# untitled4.net
KiCad netlist of a schematic drawn in EAGLE
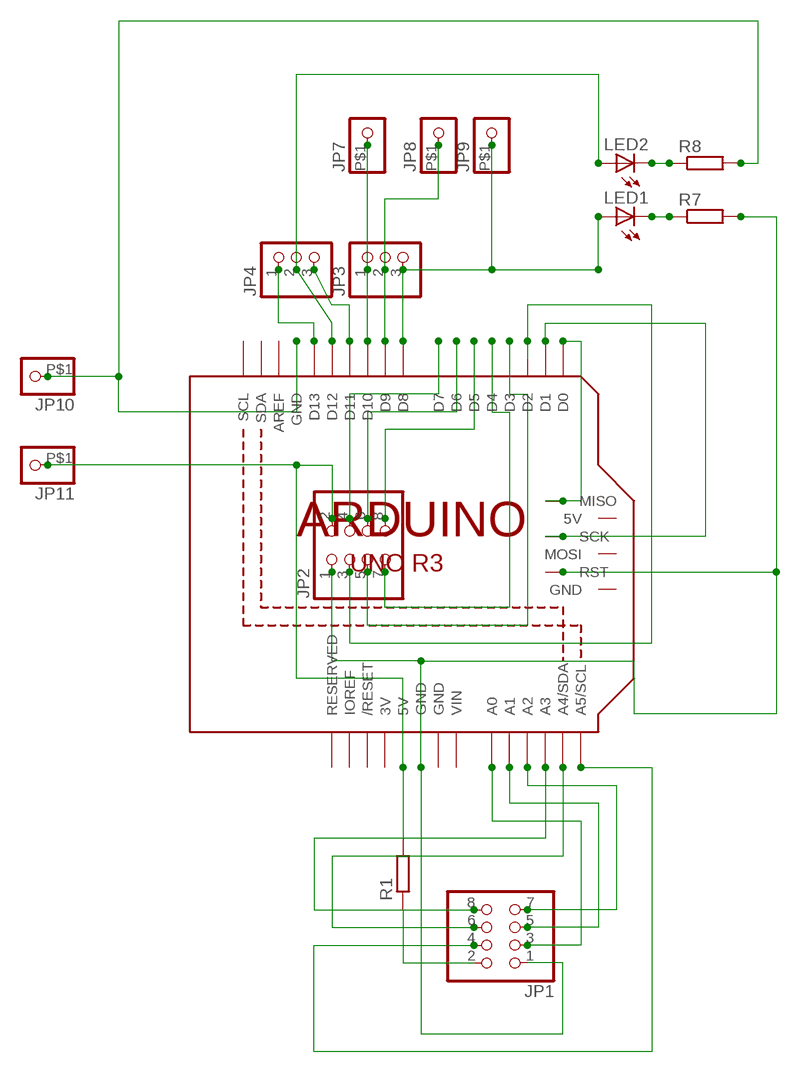
[diagram p0: schematic, sheet 1]

(export (version "E")
  (design (tool "Eeschema 10.0.6"))
  (components
    (comp (ref "JP1")
      (value "PINHD-2X4")
      (footprint "eagle-import:2X04")
      (libsource (lib "eagle-import") (part "PINHD-2X4"))
    )
    (comp (ref "JP2")
      (value "PINHD-2X4")
      (footprint "eagle-import:2X04")
      (libsource (lib "eagle-import") (part "PINHD-2X4"))
    )
    (comp (ref "JP3")
      (value "PINHD-1X3")
      (footprint "eagle-import:1X03")
      (libsource (lib "eagle-import") (part "PINHD-1X3"))
    )
    (comp (ref "JP4")
      (value "PINHD-1X3")
      (footprint "eagle-import:1X03")
      (libsource (lib "eagle-import") (part "PINHD-1X3"))
    )
    (comp (ref "JP7")
      (value "PINHD-1X1-BIGPOGO")
      (footprint "eagle-import:1X1-BIGPOGO")
      (libsource (lib "eagle-import") (part "PINHD-1X1-BIGPOGO"))
    )
    (comp (ref "JP8")
      (value "PINHD-1X1-BIGPOGO")
      (footprint "eagle-import:1X1-BIGPOGO")
      (libsource (lib "eagle-import") (part "PINHD-1X1-BIGPOGO"))
    )
    (comp (ref "JP9")
      (value "PINHD-1X1-BIGPOGO")
      (footprint "eagle-import:1X1-BIGPOGO")
      (libsource (lib "eagle-import") (part "PINHD-1X1-BIGPOGO"))
    )
    (comp (ref "JP10")
      (value "PINHD-1X1-BIGPOGO")
      (footprint "eagle-import:1X1-BIGPOGO")
      (libsource (lib "eagle-import") (part "PINHD-1X1-BIGPOGO"))
    )
    (comp (ref "JP11")
      (value "PINHD-1X1-BIGPOGO")
      (footprint "eagle-import:1X1-BIGPOGO")
      (libsource (lib "eagle-import") (part "PINHD-1X1-BIGPOGO"))
    )
    (comp (ref "LED1")
      (value "LED3MM")
      (footprint "eagle-import:LED3MM")
      (libsource (lib "eagle-import") (part "LED3MM"))
    )
    (comp (ref "LED2")
      (value "LED3MM")
      (footprint "eagle-import:LED3MM")
      (libsource (lib "eagle-import") (part "LED3MM"))
    )
    (comp (ref "M1")
      (value "ARDUINO_R3_ICSP_NODIM")
      (footprint "eagle-import:ARDUINOR3_ICSP_NODIM")
      (libsource (lib "eagle-import") (part "ARDUINO_R3_ICSP_NODIM"))
    )
    (comp (ref "R1")
      (value "R-EU_0207/10")
      (footprint "eagle-import:0207_10")
      (libsource (lib "eagle-import") (part "R-EU_0207/10"))
    )
    (comp (ref "R7")
      (value "R-EU_0207/10")
      (footprint "eagle-import:0207_10")
      (libsource (lib "eagle-import") (part "R-EU_0207/10"))
    )
    (comp (ref "R8")
      (value "R-EU_0207/10")
      (footprint "eagle-import:0207_10")
      (libsource (lib "eagle-import") (part "R-EU_0207/10"))
    )
  )
  (nets
    (net (code "1") (name "/3V") (class "Default")
      (node (ref "M1") (pin "3V") (pinfunction "3V_3V") (pintype "power_in"))
    )
    (net (code "2") (name "/GND") (class "Default")
      (node (ref "M1") (pin "GND@3") (pinfunction "GND_GND@3") (pintype "power_in"))
    )
    (net (code "3") (name "/VIN") (class "Default")
      (node (ref "M1") (pin "VIN") (pinfunction "VIN_VIN") (pintype "power_in"))
    )
    (net (code "4") (name "Net-(JP1-Pad1)") (class "Default")
      (node (ref "JP1") (pin "1") (pinfunction "1_1") (pintype "passive"))
      (node (ref "JP2") (pin "1") (pinfunction "1_1") (pintype "passive"))
      (node (ref "M1") (pin "GND@1") (pinfunction "GND_GND@1") (pintype "power_in"))
      (node (ref "R7") (pin "2") (pinfunction "2_2") (pintype "passive"))
    )
    (net (code "5") (name "Net-(JP1-Pad2)") (class "Default")
      (node (ref "JP1") (pin "2") (pinfunction "2_2") (pintype "passive"))
      (node (ref "R1") (pin "1") (pinfunction "1_1") (pintype "passive"))
    )
    (net (code "6") (name "Net-(JP1-Pad3)") (class "Default")
      (node (ref "JP1") (pin "3") (pinfunction "3_3") (pintype "passive"))
      (node (ref "M1") (pin "A0") (pinfunction "A0_A0") (pintype "bidirectional"))
    )
    (net (code "7") (name "Net-(JP1-Pad5)") (class "Default")
      (node (ref "JP1") (pin "5") (pinfunction "5_5") (pintype "passive"))
      (node (ref "M1") (pin "A1") (pinfunction "A1_A1") (pintype "bidirectional"))
    )
    (net (code "8") (name "Net-(JP1-Pad7)") (class "Default")
      (node (ref "JP1") (pin "7") (pinfunction "7_7") (pintype "passive"))
      (node (ref "M1") (pin "A2") (pinfunction "A2_A2") (pintype "bidirectional"))
    )
    (net (code "9") (name "Net-(JP1-Pad8)") (class "Default")
      (node (ref "JP1") (pin "8") (pinfunction "8_8") (pintype "passive"))
      (node (ref "M1") (pin "A3") (pinfunction "A3_A3") (pintype "bidirectional"))
    )
    (net (code "10") (name "Net-(JP2-Pad3)") (class "Default")
      (node (ref "JP2") (pin "3") (pinfunction "3_3") (pintype "passive"))
      (node (ref "M1") (pin "D2") (pinfunction "D2_D2") (pintype "bidirectional"))
    )
    (net (code "11") (name "Net-(JP2-Pad4)") (class "Default")
      (node (ref "JP2") (pin "4") (pinfunction "4_4") (pintype "passive"))
      (node (ref "M1") (pin "D7") (pinfunction "D7_D7") (pintype "bidirectional"))
    )
    (net (code "12") (name "Net-(JP2-Pad5)") (class "Default")
      (node (ref "JP2") (pin "5") (pinfunction "5_5") (pintype "passive"))
      (node (ref "M1") (pin "D3") (pinfunction "D3_D3") (pintype "bidirectional"))
    )
    (net (code "13") (name "Net-(JP2-Pad6)") (class "Default")
      (node (ref "JP2") (pin "6") (pinfunction "6_6") (pintype "passive"))
      (node (ref "M1") (pin "D6") (pinfunction "D6_D6") (pintype "bidirectional"))
    )
    (net (code "14") (name "Net-(JP2-Pad7)") (class "Default")
      (node (ref "JP2") (pin "7") (pinfunction "7_7") (pintype "passive"))
      (node (ref "M1") (pin "D4") (pinfunction "D4_D4") (pintype "bidirectional"))
    )
    (net (code "15") (name "Net-(JP2-Pad8)") (class "Default")
      (node (ref "JP2") (pin "8") (pinfunction "8_8") (pintype "passive"))
      (node (ref "M1") (pin "D5") (pinfunction "D5_D5") (pintype "bidirectional"))
    )
    (net (code "16") (name "Net-(JP4-Pad1)") (class "Default")
      (node (ref "JP4") (pin "1") (pinfunction "1_1") (pintype "passive"))
      (node (ref "M1") (pin "D13") (pinfunction "D13_D13") (pintype "bidirectional"))
    )
    (net (code "17") (name "Net-(JP4-Pad2)") (class "Default")
      (node (ref "JP4") (pin "2") (pinfunction "2_2") (pintype "passive"))
      (node (ref "LED2") (pin "A") (pinfunction "A_A") (pintype "passive"))
      (node (ref "M1") (pin "D12") (pinfunction "D12_D12") (pintype "bidirectional"))
    )
    (net (code "18") (name "Net-(JP4-Pad3)") (class "Default")
      (node (ref "JP4") (pin "3") (pinfunction "3_3") (pintype "passive"))
      (node (ref "M1") (pin "D11") (pinfunction "D11_D11") (pintype "bidirectional"))
    )
    (net (code "19") (name "Net-(JP7-1)") (class "Default")
      (node (ref "JP3") (pin "1") (pinfunction "1_1") (pintype "passive"))
      (node (ref "JP7") (pin "P$1") (pinfunction "1_P$1") (pintype "passive"))
      (node (ref "M1") (pin "D10") (pinfunction "D10_D10") (pintype "bidirectional"))
    )
    (net (code "20") (name "Net-(JP8-1)") (class "Default")
      (node (ref "JP3") (pin "2") (pinfunction "2_2") (pintype "passive"))
      (node (ref "JP8") (pin "P$1") (pinfunction "1_P$1") (pintype "passive"))
      (node (ref "M1") (pin "D9") (pinfunction "D9_D9") (pintype "bidirectional"))
    )
    (net (code "21") (name "Net-(JP9-1)") (class "Default")
      (node (ref "JP3") (pin "3") (pinfunction "3_3") (pintype "passive"))
      (node (ref "JP9") (pin "P$1") (pinfunction "1_P$1") (pintype "passive"))
      (node (ref "LED1") (pin "A") (pinfunction "A_A") (pintype "passive"))
      (node (ref "M1") (pin "D8") (pinfunction "D8_D8") (pintype "bidirectional"))
    )
    (net (code "22") (name "Net-(JP10-1)") (class "Default")
      (node (ref "JP10") (pin "P$1") (pinfunction "1_P$1") (pintype "passive"))
      (node (ref "M1") (pin "GND") (pinfunction "GND_GND") (pintype "power_in"))
      (node (ref "R8") (pin "2") (pinfunction "2_2") (pintype "passive"))
    )
    (net (code "23") (name "Net-(JP11-1)") (class "Default")
      (node (ref "JP11") (pin "P$1") (pinfunction "1_P$1") (pintype "passive"))
      (node (ref "JP2") (pin "2") (pinfunction "2_2") (pintype "passive"))
      (node (ref "M1") (pin "5V") (pinfunction "5V_5V") (pintype "power_in"))
      (node (ref "R1") (pin "2") (pinfunction "2_2") (pintype "passive"))
    )
    (net (code "24") (name "Net-(LED1-C)") (class "Default")
      (node (ref "LED1") (pin "K") (pinfunction "C_K") (pintype "passive"))
      (node (ref "R7") (pin "1") (pinfunction "1_1") (pintype "passive"))
    )
    (net (code "25") (name "Net-(LED2-C)") (class "Default")
      (node (ref "LED2") (pin "K") (pinfunction "C_K") (pintype "passive"))
      (node (ref "R8") (pin "1") (pinfunction "1_1") (pintype "passive"))
    )
    (net (code "26") (name "Net-(M1-A4{slash}SDA)") (class "Default")
      (node (ref "JP1") (pin "6") (pinfunction "6_6") (pintype "passive"))
      (node (ref "M1") (pin "A4") (pinfunction "A4/SDA_A4") (pintype "bidirectional"))
    )
    (net (code "27") (name "Net-(M1-A5{slash}SCL)") (class "Default")
      (node (ref "JP1") (pin "4") (pinfunction "4_4") (pintype "passive"))
      (node (ref "M1") (pin "A5") (pinfunction "A5/SCL_A5") (pintype "bidirectional"))
    )
    (net (code "28") (name "Net-(M1-PadD0)") (class "Default")
      (node (ref "M1") (pin "D0") (pinfunction "D0_D0") (pintype "bidirectional"))
      (node (ref "M1") (pin "MISO") (pinfunction "MISO_MISO") (pintype "passive"))
    )
    (net (code "29") (name "Net-(M1-PadD1)") (class "Default")
      (node (ref "M1") (pin "D1") (pinfunction "D1_D1") (pintype "bidirectional"))
      (node (ref "M1") (pin "SCK") (pinfunction "SCK_SCK") (pintype "passive"))
    )
    (net (code "30") (name "unconnected-(M1-5V-Pad5V_ICSP)") (class "Default")
      (node (ref "M1") (pin "5V_ICSP") (pinfunction "5V_5V_ICSP") (pintype "passive"))
    )
    (net (code "31") (name "unconnected-(M1-GND-PadGND@2)") (class "Default")
      (node (ref "M1") (pin "GND@2") (pinfunction "GND_GND@2") (pintype "passive"))
    )
    (net (code "32") (name "unconnected-(M1-PadAREF)") (class "Default")
      (node (ref "M1") (pin "AREF") (pinfunction "AREF_AREF") (pintype "bidirectional"))
    )
    (net (code "33") (name "unconnected-(M1-PadIOREF)") (class "Default")
      (node (ref "M1") (pin "IOREF") (pinfunction "IOREF_IOREF") (pintype "output"))
    )
    (net (code "34") (name "unconnected-(M1-PadMOSI)") (class "Default")
      (node (ref "M1") (pin "MOSI") (pinfunction "MOSI_MOSI") (pintype "passive"))
    )
    (net (code "35") (name "unconnected-(M1-PadRESERVED)") (class "Default")
      (node (ref "M1") (pin "RESERVED") (pinfunction "RESERVED_RESERVED") (pintype "no_connect"))
    )
    (net (code "36") (name "unconnected-(M1-PadSCL)") (class "Default")
      (node (ref "M1") (pin "SCL") (pinfunction "SCL_SCL") (pintype "bidirectional"))
    )
    (net (code "37") (name "unconnected-(M1-PadSDA)") (class "Default")
      (node (ref "M1") (pin "SDA") (pinfunction "SDA_SDA") (pintype "bidirectional"))
    )
    (net (code "38") (name "unconnected-(M1-RST-PadRESET_ICSP)") (class "Default")
      (node (ref "M1") (pin "RESET_ICSP") (pinfunction "RST_RESET_ICSP") (pintype "passive"))
    )
    (net (code "39") (name "unconnected-(M1-{slash}RESET-PadRESET)") (class "Default")
      (node (ref "M1") (pin "RESET") (pinfunction "/RESET_RESET") (pintype "bidirectional"))
    )
  )
)
